# baseboardV0_1Part2.net
KiCad netlist of a schematic drawn in Altium Designer
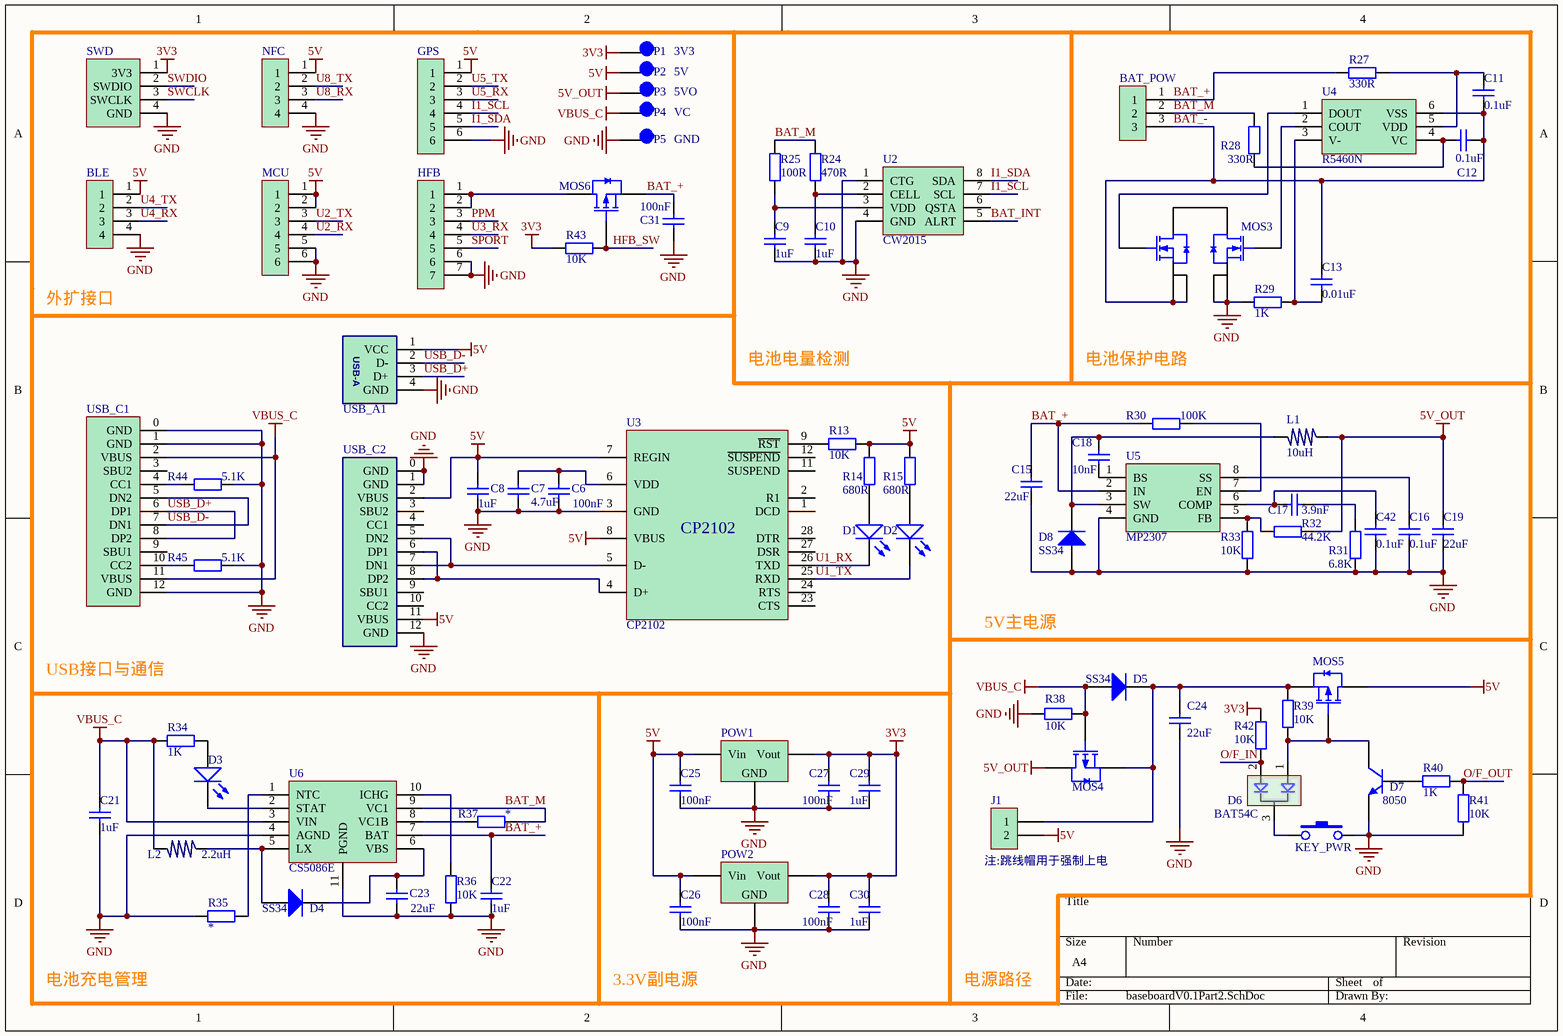
[diagram p0: baseboardV0.1Part2.SchDoc]

(export (version "E")
  (design (tool "Eeschema 10.0.6"))
  (components
    (comp (ref "BAT_POW")
      (value "XH2.54_3P_SMT_T")
      (footprint "XH2.54_3P_SMT_L")
      (libsource (lib "MT_Connector") (part "XH2.54_3P_SMT_T"))
    )
    (comp (ref "BLE")
      (value "SH1.25mm_4P")
      (footprint "SH1.25MM_4P")
      (libsource (lib "MT_Connector") (part "SH1.25mm_4P"))
    )
    (comp (ref "C6") (value "100nF") (footprint "0603_C") (libsource (lib "MT_Device") (part "0603_CAP")))
    (comp (ref "C7") (value "4.7uF") (footprint "0805_C") (libsource (lib "MT_Device") (part "0805_CAP")))
    (comp (ref "C8") (value "1uF") (footprint "0603_C") (libsource (lib "MT_Device") (part "0603_CAP")))
    (comp (ref "C9") (value "1uF") (footprint "0603_C") (libsource (lib "MT_Device") (part "0603_CAP")))
    (comp (ref "C10") (value "1uF") (footprint "0603_C") (libsource (lib "MT_Device") (part "0603_CAP")))
    (comp (ref "C11") (value "0.1uF") (footprint "0603_C") (libsource (lib "MT_Device") (part "0603_CAP")))
    (comp (ref "C12") (value "0.1uF") (footprint "0603_C") (libsource (lib "MT_Device") (part "0603_CAP")))
    (comp (ref "C13") (value "0.01uF") (footprint "0603_C") (libsource (lib "MT_Device") (part "0603_CAP")))
    (comp (ref "C15") (value "22uF") (footprint "0805_C") (libsource (lib "MT_Device") (part "0805_CAP")))
    (comp (ref "C16") (value "0.1uF") (footprint "0603_C") (libsource (lib "MT_Device") (part "0603_CAP")))
    (comp (ref "C17") (value "3.9nF") (footprint "0603_C") (libsource (lib "MT_Device") (part "0603_CAP")))
    (comp (ref "C18") (value "10nF") (footprint "0603_C") (libsource (lib "MT_Device") (part "0603_CAP")))
    (comp (ref "C19") (value "22uF") (footprint "0805_C") (libsource (lib "MT_Device") (part "0805_CAP")))
    (comp (ref "C21") (value "1uF") (footprint "0603_C") (libsource (lib "MT_Device") (part "0603_CAP")))
    (comp (ref "C22") (value "1uF") (footprint "0603_C") (libsource (lib "MT_Device") (part "0603_CAP")))
    (comp (ref "C23") (value "22uF") (footprint "0805_C") (libsource (lib "MT_Device") (part "0805_CAP")))
    (comp (ref "C24") (value "22uF") (footprint "0805_C") (libsource (lib "MT_Device") (part "0805_CAP")))
    (comp (ref "C25") (value "100nF") (footprint "0603_C") (libsource (lib "MT_Device") (part "0603_CAP")))
    (comp (ref "C26") (value "100nF") (footprint "0603_C") (libsource (lib "MT_Device") (part "0603_CAP")))
    (comp (ref "C27") (value "100nF") (footprint "0603_C") (libsource (lib "MT_Device") (part "0603_CAP")))
    (comp (ref "C28") (value "100nF") (footprint "0603_C") (libsource (lib "MT_Device") (part "0603_CAP")))
    (comp (ref "C29") (value "1uF") (footprint "0603_C") (libsource (lib "MT_Device") (part "0603_CAP")))
    (comp (ref "C30") (value "1uF") (footprint "0603_C") (libsource (lib "MT_Device") (part "0603_CAP")))
    (comp (ref "C31") (value "100nF") (footprint "0603_C") (libsource (lib "MT_Device") (part "0603_CAP")))
    (comp (ref "C42") (value "0.1uF") (footprint "0603_C") (libsource (lib "MT_Device") (part "0603_CAP")))
    (comp (ref "D1")
      (value "0805_LED")
      (footprint "0805_LED")
      (libsource (lib "MT_Device") (part "0805_LED"))
    )
    (comp (ref "D2")
      (value "0805_LED")
      (footprint "0805_LED")
      (libsource (lib "MT_Device") (part "0805_LED"))
    )
    (comp (ref "D3")
      (value "0805_LED")
      (footprint "0805_LED")
      (libsource (lib "MT_Device") (part "0805_LED"))
    )
    (comp (ref "D4") (value "SS34") (footprint "DO214_SMC") (libsource (lib "MT_Device") (part "SS34_DO214")))
    (comp (ref "D5") (value "SS34") (footprint "DO214_SMC") (libsource (lib "MT_Device") (part "SS34_DO214")))
    (comp (ref "D6") (value "BAT54C") (footprint "BAT54C") (libsource (lib "MT_Device") (part "BAT54C")))
    (comp (ref "D7")
      (value "8050")
      (footprint "SOT23")
      (libsource (lib "MT_Device") (part "NPN_SS8050_SOT23"))
    )
    (comp (ref "D8") (value "SS34") (footprint "DO214_SMC") (libsource (lib "MT_Device") (part "SS34_DO214")))
    (comp (ref "GPS")
      (value "SH1.25mm_6P")
      (footprint "SH1.25MM_6P")
      (libsource (lib "MT_Connector") (part "SH1.25mm_6P"))
    )
    (comp (ref "HFB")
      (value "SH1.25mm_7P")
      (footprint "SH1.25MM_7P")
      (libsource (lib "MT_Connector") (part "SH1.25mm_7P"))
    )
    (comp (ref "J1")
      (value "Header_2.54_2P")
      (footprint "HDR1_2P")
      (libsource (lib "MT_Connector") (part "Header_2.54_2P"))
    )
    (comp (ref "KEY_PWR")
      (value "KEY_S_6*6")
      (footprint "KEY_S_6*6")
      (libsource (lib "MT_Device") (part "KEY_S_6*6"))
    )
    (comp (ref "L1") (value "10uH") (footprint "0630_L") (libsource (lib "MT_Device") (part "0630_L")))
    (comp (ref "L2") (value "2.2uH") (footprint "0630_L") (libsource (lib "MT_Device") (part "0630_L")))
    (comp (ref "MCU")
      (value "SH1.25mm_6P")
      (footprint "SH1.25MM_6P")
      (libsource (lib "MT_Connector") (part "SH1.25mm_6P"))
    )
    (comp (ref "MOS3")
      (value "MOSN_8205A_TSSOP8")
      (footprint "TSSOP-8")
      (libsource (lib "MT_Device") (part "MOSN_8205A_TSSOP8"))
    )
    (comp (ref "MOS4")
      (value "MOSP_AO4419_SOIC8")
      (footprint "SOIC8_MOS")
      (libsource (lib "MT_Device") (part "MOSP_AO4419_SOIC8"))
    )
    (comp (ref "MOS5")
      (value "MOSP_AO4419_SOIC8")
      (footprint "SOIC8_MOS")
      (libsource (lib "MT_Device") (part "MOSP_AO4419_SOIC8"))
    )
    (comp (ref "MOS6")
      (value "MOSP_AO4419_SOIC8")
      (footprint "SOIC8_MOS")
      (libsource (lib "MT_Device") (part "MOSP_AO4419_SOIC8"))
    )
    (comp (ref "MTSWD") (value "SWD") (footprint "MT_SWD_1") (libsource (lib "MT_Module") (part "MT_SWD_1")))
    (comp (ref "NFC")
      (value "SH1.25mm_4P")
      (footprint "SH1.25MM_4P")
      (libsource (lib "MT_Connector") (part "SH1.25mm_4P"))
    )
    (comp (ref "P1")
      (value "3V3")
      (footprint "TEST_POINT_2mm")
      (libsource (lib "MT_Connector") (part "TEST_POINT_2mm"))
    )
    (comp (ref "P2")
      (value "5V")
      (footprint "TEST_POINT_2mm")
      (libsource (lib "MT_Connector") (part "TEST_POINT_2mm"))
    )
    (comp (ref "P3")
      (value "5VO")
      (footprint "TEST_POINT_2mm")
      (libsource (lib "MT_Connector") (part "TEST_POINT_2mm"))
    )
    (comp (ref "P4")
      (value "VC")
      (footprint "TEST_POINT_2mm")
      (libsource (lib "MT_Connector") (part "TEST_POINT_2mm"))
    )
    (comp (ref "P5")
      (value "GND")
      (footprint "TEST_POINT_2mm")
      (libsource (lib "MT_Connector") (part "TEST_POINT_2mm"))
    )
    (comp (ref "POW1")
      (value "AMS1117_3.3")
      (footprint "SOT223")
      (libsource (lib "MT_Device") (part "AMS1117_3.3"))
    )
    (comp (ref "POW2")
      (value "AMS1117_3.3")
      (footprint "SOT223")
      (libsource (lib "MT_Device") (part "AMS1117_3.3"))
    )
    (comp (ref "R13") (value "10K") (footprint "0603_R") (libsource (lib "") (part "0603_RES_3")))
    (comp (ref "R14") (value "680R") (footprint "0603_R") (libsource (lib "") (part "0603_RES_1")))
    (comp (ref "R15") (value "680R") (footprint "0603_R") (libsource (lib "") (part "0603_RES_1")))
    (comp (ref "R24") (value "470R") (footprint "0603_R") (libsource (lib "MT_Device") (part "0603_RES")))
    (comp (ref "R25") (value "100R") (footprint "0603_R") (libsource (lib "MT_Device") (part "0603_RES")))
    (comp (ref "R27") (value "330R") (footprint "0603_R") (libsource (lib "") (part "0603_RES_2")))
    (comp (ref "R28") (value "330R") (footprint "0603_R") (libsource (lib "") (part "0603_RES_1")))
    (comp (ref "R29") (value "1K") (footprint "0603_R") (libsource (lib "") (part "0603_RES_2")))
    (comp (ref "R30") (value "100K") (footprint "0603_R") (libsource (lib "") (part "0603_RES_2")))
    (comp (ref "R31") (value "6.8K") (footprint "0603_R") (libsource (lib "") (part "0603_RES_1")))
    (comp (ref "R32") (value "44.2K") (footprint "0603_R") (libsource (lib "") (part "0603_RES_3")))
    (comp (ref "R33") (value "10K") (footprint "0603_R") (libsource (lib "") (part "0603_RES_1")))
    (comp (ref "R34") (value "1K") (footprint "0603_R") (libsource (lib "") (part "0603_RES_3")))
    (comp (ref "R35") (value "*") (footprint "0603_R") (libsource (lib "") (part "0603_RES_3")))
    (comp (ref "R36") (value "10K") (footprint "0603_R") (libsource (lib "MT_Device") (part "0603_RES")))
    (comp (ref "R37") (value "*") (footprint "0603_R") (libsource (lib "") (part "0603_RES_3")))
    (comp (ref "R38") (value "10K") (footprint "0603_R") (libsource (lib "") (part "0603_RES_3")))
    (comp (ref "R39") (value "10K") (footprint "0603_R") (libsource (lib "") (part "0603_RES_1")))
    (comp (ref "R40") (value "1K") (footprint "0603_R") (libsource (lib "") (part "0603_RES_2")))
    (comp (ref "R41") (value "10K") (footprint "0603_R") (libsource (lib "") (part "0603_RES_1")))
    (comp (ref "R42") (value "10K") (footprint "0603_R") (libsource (lib "") (part "0603_RES_1")))
    (comp (ref "R43") (value "10K") (footprint "0603_R") (libsource (lib "") (part "0603_RES_2")))
    (comp (ref "R44") (value "5.1K") (footprint "0603_R") (libsource (lib "") (part "0603_RES_2")))
    (comp (ref "R45") (value "5.1K") (footprint "0603_R") (libsource (lib "") (part "0603_RES_2")))
    (comp (ref "U2")
      (value "CW2015")
      (footprint "CW2015_TDFN")
      (libsource (lib "MT_Chip") (part "CW2015_TDFN"))
    )
    (comp (ref "U3") (value "CP2102") (footprint "QFN28") (libsource (lib "MT_Chip") (part "CP2102_QFN28")))
    (comp (ref "U4")
      (value "R5460N")
      (footprint "SOT_23_6")
      (description "2-CELL PROTECTOR")
      (libsource (lib "MT_Chip") (part "R5460N"))
    )
    (comp (ref "U5") (value "MP2307") (footprint "SOIC8N") (libsource (lib "MT_Chip") (part "MP2307")))
    (comp (ref "U6") (value "CS5086E") (footprint "ESOP10L") (libsource (lib "MT_Chip") (part "CS5086E")))
    (comp (ref "USB_A1")
      (value "USB_A_SMT")
      (footprint "USB_A_SMT")
      (libsource (lib "MT_Device") (part "USB_A_SMT"))
    )
    (comp (ref "USB_C1")
      (value "USB_C_16P_SMT")
      (footprint "USB_C_16PIN_SMT")
      (libsource (lib "MT_Device") (part "USB_C_16P_SMT"))
    )
    (comp (ref "USB_C2")
      (value "USB_C_16P_SMT")
      (footprint "USB_C_16PIN_SMT")
      (libsource (lib "") (part "USB_C_16P_SMT_1"))
    )
  )
  (nets
    (net (code "1") (name "/BAT_+") (class "Default")
      (node (ref "BAT_POW") (pin "1") (pinfunction "1_1") (pintype "passive"))
      (node (ref "C15") (pin "2") (pinfunction "2_2") (pintype "passive"))
      (node (ref "C22") (pin "2") (pinfunction "2_2") (pintype "passive"))
      (node (ref "C31") (pin "2") (pinfunction "2_2") (pintype "passive"))
      (node (ref "MOS6") (pin "3") (pinfunction "S_3") (pintype "passive"))
      (node (ref "R27") (pin "2") (pinfunction "2_2") (pintype "passive"))
      (node (ref "R30") (pin "2") (pinfunction "2_2") (pintype "passive"))
      (node (ref "U5") (pin "2") (pinfunction "IN_2") (pintype "passive"))
      (node (ref "U6") (pin "7") (pinfunction "BAT_7") (pintype "passive"))
    )
    (net (code "2") (name "/BAT_-") (class "Default")
      (node (ref "BAT_POW") (pin "3") (pinfunction "3_3") (pintype "passive"))
      (node (ref "C11") (pin "1") (pinfunction "1_1") (pintype "passive"))
      (node (ref "C12") (pin "1") (pinfunction "1_1") (pintype "passive"))
      (node (ref "C13") (pin "2") (pinfunction "2_2") (pintype "passive"))
      (node (ref "MOS3") (pin "2") (pinfunction "S1_2") (pintype "passive"))
      (node (ref "MOS3") (pin "3") (pinfunction "S1_3") (pintype "passive"))
      (node (ref "U4") (pin "6") (pinfunction "VSS_6") (pintype "passive"))
    )
    (net (code "3") (name "/BAT_INT") (class "Default")
      (node (ref "U2") (pin "5") (pinfunction "ALRT_5") (pintype "passive"))
    )
    (net (code "4") (name "/BAT_M") (class "Default")
      (node (ref "BAT_POW") (pin "2") (pinfunction "2_2") (pintype "passive"))
      (node (ref "R24") (pin "1") (pinfunction "1_1") (pintype "passive"))
      (node (ref "R25") (pin "1") (pinfunction "1_1") (pintype "passive"))
      (node (ref "R28") (pin "2") (pinfunction "2_2") (pintype "passive"))
      (node (ref "R37") (pin "2") (pinfunction "2_2") (pintype "passive"))
      (node (ref "U6") (pin "9") (pinfunction "VC1_9") (pintype "passive"))
    )
    (net (code "5") (name "/HFB_SW") (class "Default")
      (node (ref "MOS6") (pin "1") (pinfunction "G_1") (pintype "passive"))
      (node (ref "R43") (pin "1") (pinfunction "1_1") (pintype "passive"))
    )
    (net (code "6") (name "/I1_SCL") (class "Default")
      (node (ref "GPS") (pin "4") (pinfunction "4_4") (pintype "passive"))
      (node (ref "U2") (pin "7") (pinfunction "SCL_7") (pintype "passive"))
    )
    (net (code "7") (name "/I1_SDA") (class "Default")
      (node (ref "GPS") (pin "5") (pinfunction "5_5") (pintype "passive"))
      (node (ref "U2") (pin "8") (pinfunction "SDA_8") (pintype "passive"))
    )
    (net (code "8") (name "/O{slash}F_IN") (class "Default")
      (node (ref "D6") (pin "2") (pinfunction "2_2") (pintype "passive"))
      (node (ref "R42") (pin "1") (pinfunction "1_1") (pintype "passive"))
    )
    (net (code "9") (name "/O{slash}F_OUT") (class "Default")
      (node (ref "R40") (pin "1") (pinfunction "1_1") (pintype "passive"))
      (node (ref "R41") (pin "2") (pinfunction "2_2") (pintype "passive"))
    )
    (net (code "10") (name "/PPM") (class "Default")
      (node (ref "HFB") (pin "3") (pinfunction "3_3") (pintype "passive"))
    )
    (net (code "11") (name "/SPORT") (class "Default")
      (node (ref "HFB") (pin "5") (pinfunction "5_5") (pintype "passive"))
    )
    (net (code "12") (name "/SWCLK") (class "Default")
      (node (ref "MTSWD") (pin "3") (pinfunction "SWCLK_3") (pintype "passive"))
    )
    (net (code "13") (name "/SWDIO") (class "Default")
      (node (ref "MTSWD") (pin "2") (pinfunction "SWDIO_2") (pintype "passive"))
    )
    (net (code "14") (name "/U1_RX") (class "Default")
      (node (ref "D1") (pin "K") (pinfunction "K_K") (pintype "passive"))
      (node (ref "U3") (pin "26") (pinfunction "TXD_26") (pintype "passive"))
    )
    (net (code "15") (name "/U1_TX") (class "Default")
      (node (ref "D2") (pin "K") (pinfunction "K_K") (pintype "passive"))
      (node (ref "U3") (pin "25") (pinfunction "RXD_25") (pintype "passive"))
    )
    (net (code "16") (name "/U2_RX") (class "Default")
      (node (ref "MCU") (pin "4") (pinfunction "4_4") (pintype "passive"))
    )
    (net (code "17") (name "/U2_TX") (class "Default")
      (node (ref "MCU") (pin "3") (pinfunction "3_3") (pintype "passive"))
    )
    (net (code "18") (name "/U3_RX") (class "Default")
      (node (ref "HFB") (pin "4") (pinfunction "4_4") (pintype "passive"))
    )
    (net (code "19") (name "/U4_RX") (class "Default")
      (node (ref "BLE") (pin "3") (pinfunction "3_3") (pintype "passive"))
    )
    (net (code "20") (name "/U4_TX") (class "Default")
      (node (ref "BLE") (pin "2") (pinfunction "2_2") (pintype "passive"))
    )
    (net (code "21") (name "/U5_RX") (class "Default")
      (node (ref "GPS") (pin "3") (pinfunction "3_3") (pintype "passive"))
    )
    (net (code "22") (name "/U5_TX") (class "Default")
      (node (ref "GPS") (pin "2") (pinfunction "2_2") (pintype "passive"))
    )
    (net (code "23") (name "/U8_RX") (class "Default")
      (node (ref "NFC") (pin "3") (pinfunction "3_3") (pintype "passive"))
    )
    (net (code "24") (name "/U8_TX") (class "Default")
      (node (ref "NFC") (pin "2") (pinfunction "2_2") (pintype "passive"))
    )
    (net (code "25") (name "/USB_D+") (class "Default")
      (node (ref "USB_A1") (pin "3") (pinfunction "D+_3") (pintype "passive"))
      (node (ref "USB_C1") (pin "6") (pinfunction "DP1_6") (pintype "passive"))
      (node (ref "USB_C1") (pin "8") (pinfunction "DP2_8") (pintype "passive"))
    )
    (net (code "26") (name "/USB_D-") (class "Default")
      (node (ref "USB_A1") (pin "2") (pinfunction "D-_2") (pintype "passive"))
      (node (ref "USB_C1") (pin "5") (pinfunction "DN2_5") (pintype "passive"))
      (node (ref "USB_C1") (pin "7") (pinfunction "DN1_7") (pintype "passive"))
    )
    (net (code "27") (name "3V3") (class "Default")
      (node (ref "C27") (pin "2") (pinfunction "2_2") (pintype "passive"))
      (node (ref "C28") (pin "2") (pinfunction "2_2") (pintype "passive"))
      (node (ref "C29") (pin "2") (pinfunction "2_2") (pintype "passive"))
      (node (ref "C30") (pin "2") (pinfunction "2_2") (pintype "passive"))
      (node (ref "MTSWD") (pin "1") (pinfunction "3V3_1") (pintype "passive"))
      (node (ref "P1") (pin "1") (pinfunction "1_1") (pintype "passive"))
      (node (ref "POW1") (pin "2") (pinfunction "Vout_2") (pintype "passive"))
      (node (ref "POW2") (pin "2") (pinfunction "Vout_2") (pintype "passive"))
      (node (ref "R42") (pin "2") (pinfunction "2_2") (pintype "passive"))
      (node (ref "R43") (pin "2") (pinfunction "2_2") (pintype "passive"))
    )
    (net (code "28") (name "5V") (class "Default")
      (node (ref "BLE") (pin "1") (pinfunction "1_1") (pintype "passive"))
      (node (ref "C25") (pin "2") (pinfunction "2_2") (pintype "passive"))
      (node (ref "C26") (pin "2") (pinfunction "2_2") (pintype "passive"))
      (node (ref "C8") (pin "2") (pinfunction "2_2") (pintype "passive"))
      (node (ref "GPS") (pin "1") (pinfunction "1_1") (pintype "passive"))
      (node (ref "J1") (pin "2") (pinfunction "2_2") (pintype "passive"))
      (node (ref "MCU") (pin "1") (pinfunction "1_1") (pintype "passive"))
      (node (ref "MCU") (pin "2") (pinfunction "2_2") (pintype "passive"))
      (node (ref "MOS5") (pin "2") (pinfunction "D_2") (pintype "passive"))
      (node (ref "NFC") (pin "1") (pinfunction "1_1") (pintype "passive"))
      (node (ref "P2") (pin "1") (pinfunction "1_1") (pintype "passive"))
      (node (ref "POW1") (pin "3") (pinfunction "Vin_3") (pintype "passive"))
      (node (ref "POW2") (pin "3") (pinfunction "Vin_3") (pintype "passive"))
      (node (ref "R13") (pin "2") (pinfunction "2_2") (pintype "passive"))
      (node (ref "R14") (pin "2") (pinfunction "2_2") (pintype "passive"))
      (node (ref "R15") (pin "2") (pinfunction "2_2") (pintype "passive"))
      (node (ref "U3") (pin "7") (pinfunction "REGIN_7") (pintype "passive"))
      (node (ref "U3") (pin "8") (pinfunction "VBUS_8") (pintype "passive"))
      (node (ref "USB_A1") (pin "1") (pinfunction "VCC_1") (pintype "passive"))
      (node (ref "USB_C2") (pin "11") (pinfunction "VBUS_11") (pintype "passive"))
      (node (ref "USB_C2") (pin "2") (pinfunction "VBUS_2") (pintype "passive"))
    )
    (net (code "29") (name "5V_OUT") (class "Default")
      (node (ref "C19") (pin "2") (pinfunction "2_2") (pintype "passive"))
      (node (ref "L1") (pin "1") (pintype "passive"))
      (node (ref "MOS4") (pin "2") (pinfunction "D_2") (pintype "passive"))
      (node (ref "P3") (pin "1") (pinfunction "1_1") (pintype "passive"))
      (node (ref "R32") (pin "2") (pinfunction "2_2") (pintype "passive"))
    )
    (net (code "30") (name "GND") (class "Default")
      (node (ref "BLE") (pin "4") (pinfunction "4_4") (pintype "passive"))
      (node (ref "C10") (pin "1") (pinfunction "1_1") (pintype "passive"))
      (node (ref "C15") (pin "1") (pinfunction "1_1") (pintype "passive"))
      (node (ref "C16") (pin "2") (pinfunction "2_2") (pintype "passive"))
      (node (ref "C19") (pin "1") (pinfunction "1_1") (pintype "passive"))
      (node (ref "C21") (pin "1") (pinfunction "1_1") (pintype "passive"))
      (node (ref "C22") (pin "1") (pinfunction "1_1") (pintype "passive"))
      (node (ref "C23") (pin "1") (pinfunction "1_1") (pintype "passive"))
      (node (ref "C24") (pin "1") (pinfunction "1_1") (pintype "passive"))
      (node (ref "C25") (pin "1") (pinfunction "1_1") (pintype "passive"))
      (node (ref "C26") (pin "1") (pinfunction "1_1") (pintype "passive"))
      (node (ref "C27") (pin "1") (pinfunction "1_1") (pintype "passive"))
      (node (ref "C28") (pin "1") (pinfunction "1_1") (pintype "passive"))
      (node (ref "C29") (pin "1") (pinfunction "1_1") (pintype "passive"))
      (node (ref "C30") (pin "1") (pinfunction "1_1") (pintype "passive"))
      (node (ref "C31") (pin "1") (pinfunction "1_1") (pintype "passive"))
      (node (ref "C42") (pin "2") (pinfunction "2_2") (pintype "passive"))
      (node (ref "C6") (pin "1") (pinfunction "1_1") (pintype "passive"))
      (node (ref "C7") (pin "2") (pinfunction "2_2") (pintype "passive"))
      (node (ref "C8") (pin "1") (pinfunction "1_1") (pintype "passive"))
      (node (ref "C9") (pin "1") (pinfunction "1_1") (pintype "passive"))
      (node (ref "D7") (pin "2") (pinfunction "E_2") (pintype "passive"))
      (node (ref "D8") (pin "1") (pinfunction "A_1") (pintype "passive"))
      (node (ref "GPS") (pin "6") (pinfunction "6_6") (pintype "passive"))
      (node (ref "HFB") (pin "6") (pinfunction "6_6") (pintype "passive"))
      (node (ref "HFB") (pin "7") (pinfunction "7_7") (pintype "passive"))
      (node (ref "KEY_PWR") (pin "2") (pinfunction "2_2") (pintype "passive"))
      (node (ref "MCU") (pin "5") (pinfunction "5_5") (pintype "passive"))
      (node (ref "MCU") (pin "6") (pinfunction "6_6") (pintype "passive"))
      (node (ref "MOS3") (pin "6") (pinfunction "S2_6") (pintype "passive"))
      (node (ref "MOS3") (pin "7") (pinfunction "S2_7") (pintype "passive"))
      (node (ref "MTSWD") (pin "4") (pinfunction "GND_4") (pintype "passive"))
      (node (ref "NFC") (pin "4") (pinfunction "4_4") (pintype "passive"))
      (node (ref "P5") (pin "1") (pinfunction "1_1") (pintype "passive"))
      (node (ref "POW1") (pin "1") (pinfunction "GND_1") (pintype "passive"))
      (node (ref "POW2") (pin "1") (pinfunction "GND_1") (pintype "passive"))
      (node (ref "R29") (pin "2") (pinfunction "2_2") (pintype "passive"))
      (node (ref "R31") (pin "1") (pinfunction "1_1") (pintype "passive"))
      (node (ref "R33") (pin "1") (pinfunction "1_1") (pintype "passive"))
      (node (ref "R35") (pin "1") (pinfunction "1_1") (pintype "passive"))
      (node (ref "R36") (pin "2") (pinfunction "2_2") (pintype "passive"))
      (node (ref "R38") (pin "1") (pinfunction "1_1") (pintype "passive"))
      (node (ref "R41") (pin "1") (pinfunction "1_1") (pintype "passive"))
      (node (ref "R44") (pin "1") (pinfunction "1_1") (pintype "passive"))
      (node (ref "R45") (pin "1") (pinfunction "1_1") (pintype "passive"))
      (node (ref "U2") (pin "1") (pinfunction "CTG_1") (pintype "passive"))
      (node (ref "U2") (pin "4") (pinfunction "GND_4") (pintype "passive"))
      (node (ref "U3") (pin "3") (pinfunction "GND_3") (pintype "passive"))
      (node (ref "U5") (pin "4") (pinfunction "GND_4") (pintype "passive"))
      (node (ref "U6") (pin "11") (pinfunction "PGND_11") (pintype "passive"))
      (node (ref "U6") (pin "4") (pinfunction "AGND_4") (pintype "passive"))
      (node (ref "USB_A1") (pin "4") (pinfunction "GND_4") (pintype "passive"))
      (node (ref "USB_C1") (pin "0") (pinfunction "GND_0") (pintype "passive"))
      (node (ref "USB_C1") (pin "1") (pinfunction "GND_1") (pintype "passive"))
      (node (ref "USB_C1") (pin "12") (pinfunction "GND_12") (pintype "passive"))
      (node (ref "USB_C2") (pin "0") (pinfunction "GND_0") (pintype "passive"))
      (node (ref "USB_C2") (pin "1") (pinfunction "GND_1") (pintype "passive"))
      (node (ref "USB_C2") (pin "12") (pinfunction "GND_12") (pintype "passive"))
    )
    (net (code "31") (name "Net-(C17-Pad2)") (class "Default")
      (node (ref "C17") (pin "2") (pinfunction "2_2") (pintype "passive"))
      (node (ref "R31") (pin "2") (pinfunction "2_2") (pintype "passive"))
    )
    (net (code "32") (name "Net-(D1-PadA)") (class "Default")
      (node (ref "D1") (pin "A") (pinfunction "A_A") (pintype "passive"))
      (node (ref "R14") (pin "1") (pinfunction "1_1") (pintype "passive"))
    )
    (net (code "33") (name "Net-(D2-PadA)") (class "Default")
      (node (ref "D2") (pin "A") (pinfunction "A_A") (pintype "passive"))
      (node (ref "R15") (pin "1") (pinfunction "1_1") (pintype "passive"))
    )
    (net (code "34") (name "Net-(D3-PadA)") (class "Default")
      (node (ref "D3") (pin "A") (pinfunction "A_A") (pintype "passive"))
      (node (ref "R34") (pin "2") (pinfunction "2_2") (pintype "passive"))
    )
    (net (code "35") (name "Net-(D4-A)") (class "Default")
      (node (ref "D4") (pin "1") (pinfunction "A_1") (pintype "passive"))
      (node (ref "L2") (pin "1") (pintype "passive"))
      (node (ref "U6") (pin "5") (pinfunction "LX_5") (pintype "passive"))
    )
    (net (code "36") (name "Net-(D4-K)") (class "Default")
      (node (ref "C23") (pin "2") (pinfunction "2_2") (pintype "passive"))
      (node (ref "D4") (pin "2") (pinfunction "K_2") (pintype "passive"))
      (node (ref "U6") (pin "6") (pinfunction "VBS_6") (pintype "passive"))
    )
    (net (code "37") (name "Net-(D5-K)") (class "Default")
      (node (ref "C24") (pin "2") (pinfunction "2_2") (pintype "passive"))
      (node (ref "D5") (pin "2") (pinfunction "K_2") (pintype "passive"))
      (node (ref "J1") (pin "1") (pinfunction "1_1") (pintype "passive"))
      (node (ref "MOS4") (pin "3") (pinfunction "S_3") (pintype "passive"))
      (node (ref "MOS5") (pin "3") (pinfunction "S_3") (pintype "passive"))
      (node (ref "R39") (pin "2") (pinfunction "2_2") (pintype "passive"))
    )
    (net (code "38") (name "Net-(D6-Pad3)") (class "Default")
      (node (ref "D6") (pin "3") (pinfunction "3_3") (pintype "passive"))
      (node (ref "KEY_PWR") (pin "1") (pinfunction "1_1") (pintype "passive"))
    )
    (net (code "39") (name "Net-(D7-B)") (class "Default")
      (node (ref "D7") (pin "1") (pinfunction "B_1") (pintype "passive"))
      (node (ref "R40") (pin "2") (pinfunction "2_2") (pintype "passive"))
    )
    (net (code "40") (name "Net-(D7-C)") (class "Default")
      (node (ref "D6") (pin "1") (pinfunction "1_1") (pintype "passive"))
      (node (ref "D7") (pin "3") (pinfunction "C_3") (pintype "passive"))
      (node (ref "MOS5") (pin "1") (pinfunction "G_1") (pintype "passive"))
      (node (ref "R39") (pin "1") (pinfunction "1_1") (pintype "passive"))
    )
    (net (code "41") (name "Net-(D8-K)") (class "Default")
      (node (ref "C18") (pin "1") (pinfunction "1_1") (pintype "passive"))
      (node (ref "D8") (pin "2") (pinfunction "K_2") (pintype "passive"))
      (node (ref "L1") (pin "2") (pintype "passive"))
      (node (ref "U5") (pin "3") (pinfunction "SW_3") (pintype "passive"))
    )
    (net (code "42") (name "Net-(MOS3-G1)") (class "Default")
      (node (ref "MOS3") (pin "4") (pinfunction "G1_4") (pintype "passive"))
      (node (ref "U4") (pin "1") (pinfunction "DOUT_1") (pintype "passive"))
    )
    (net (code "43") (name "Net-(MOS3-G2)") (class "Default")
      (node (ref "MOS3") (pin "5") (pinfunction "G2_5") (pintype "passive"))
      (node (ref "U4") (pin "2") (pinfunction "COUT_2") (pintype "passive"))
    )
    (net (code "44") (name "Net-(MOS6-D)") (class "Default")
      (node (ref "HFB") (pin "1") (pinfunction "1_1") (pintype "passive"))
      (node (ref "HFB") (pin "2") (pinfunction "2_2") (pintype "passive"))
      (node (ref "MOS6") (pin "2") (pinfunction "D_2") (pintype "passive"))
    )
    (net (code "45") (name "Net-(U2-CELL)") (class "Default")
      (node (ref "C10") (pin "2") (pinfunction "2_2") (pintype "passive"))
      (node (ref "R24") (pin "2") (pinfunction "2_2") (pintype "passive"))
      (node (ref "U2") (pin "2") (pinfunction "CELL_2") (pintype "passive"))
    )
    (net (code "46") (name "Net-(U2-VDD)") (class "Default")
      (node (ref "C9") (pin "2") (pinfunction "2_2") (pintype "passive"))
      (node (ref "R25") (pin "2") (pinfunction "2_2") (pintype "passive"))
      (node (ref "U2") (pin "3") (pinfunction "VDD_3") (pintype "passive"))
    )
    (net (code "47") (name "Net-(U3-D+)") (class "Default")
      (node (ref "U3") (pin "4") (pinfunction "D+_4") (pintype "passive"))
      (node (ref "USB_C2") (pin "6") (pinfunction "DP1_6") (pintype "passive"))
      (node (ref "USB_C2") (pin "8") (pinfunction "DP2_8") (pintype "passive"))
    )
    (net (code "48") (name "Net-(U3-D-)") (class "Default")
      (node (ref "U3") (pin "5") (pinfunction "D-_5") (pintype "passive"))
      (node (ref "USB_C2") (pin "5") (pinfunction "DN2_5") (pintype "passive"))
      (node (ref "USB_C2") (pin "7") (pinfunction "DN1_7") (pintype "passive"))
    )
    (net (code "49") (name "Net-(U3-VDD)") (class "Default")
      (node (ref "C6") (pin "2") (pinfunction "2_2") (pintype "passive"))
      (node (ref "C7") (pin "1") (pinfunction "1_1") (pintype "passive"))
      (node (ref "U3") (pin "6") (pinfunction "VDD_6") (pintype "passive"))
    )
    (net (code "50") (name "Net-(U3-~{RST})") (class "Default")
      (node (ref "R13") (pin "1") (pinfunction "1_1") (pintype "passive"))
      (node (ref "U3") (pin "9") (pinfunction "~{RST}_9") (pintype "passive"))
    )
    (net (code "51") (name "Net-(U4-V-)") (class "Default")
      (node (ref "C13") (pin "1") (pinfunction "1_1") (pintype "passive"))
      (node (ref "R29") (pin "1") (pinfunction "1_1") (pintype "passive"))
      (node (ref "U4") (pin "3") (pinfunction "V-_3") (pintype "passive"))
    )
    (net (code "52") (name "Net-(U4-VC)") (class "Default")
      (node (ref "C12") (pin "2") (pinfunction "2_2") (pintype "passive"))
      (node (ref "R28") (pin "1") (pinfunction "1_1") (pintype "passive"))
      (node (ref "U4") (pin "4") (pinfunction "VC_4") (pintype "passive"))
    )
    (net (code "53") (name "Net-(U4-VDD)") (class "Default")
      (node (ref "C11") (pin "2") (pinfunction "2_2") (pintype "passive"))
      (node (ref "R27") (pin "1") (pinfunction "1_1") (pintype "passive"))
      (node (ref "U4") (pin "5") (pinfunction "VDD_5") (pintype "passive"))
    )
    (net (code "54") (name "Net-(U5-BS)") (class "Default")
      (node (ref "C18") (pin "2") (pinfunction "2_2") (pintype "passive"))
      (node (ref "U5") (pin "1") (pinfunction "BS_1") (pintype "passive"))
    )
    (net (code "55") (name "Net-(U5-COMP)") (class "Default")
      (node (ref "C17") (pin "1") (pinfunction "1_1") (pintype "passive"))
      (node (ref "C42") (pin "1") (pinfunction "1_1") (pintype "passive"))
      (node (ref "U5") (pin "6") (pinfunction "COMP_6") (pintype "passive"))
    )
    (net (code "56") (name "Net-(U5-EN)") (class "Default")
      (node (ref "R30") (pin "1") (pinfunction "1_1") (pintype "passive"))
      (node (ref "U5") (pin "7") (pinfunction "EN_7") (pintype "passive"))
    )
    (net (code "57") (name "Net-(U5-FB)") (class "Default")
      (node (ref "R32") (pin "1") (pinfunction "1_1") (pintype "passive"))
      (node (ref "R33") (pin "2") (pinfunction "2_2") (pintype "passive"))
      (node (ref "U5") (pin "5") (pinfunction "FB_5") (pintype "passive"))
    )
    (net (code "58") (name "Net-(U5-SS)") (class "Default")
      (node (ref "C16") (pin "1") (pinfunction "1_1") (pintype "passive"))
      (node (ref "U5") (pin "8") (pinfunction "SS_8") (pintype "passive"))
    )
    (net (code "59") (name "Net-(U6-ICHG)") (class "Default")
      (node (ref "R36") (pin "1") (pinfunction "1_1") (pintype "passive"))
      (node (ref "U6") (pin "10") (pinfunction "ICHG_10") (pintype "passive"))
    )
    (net (code "60") (name "Net-(U6-NTC)") (class "Default")
      (node (ref "R35") (pin "2") (pinfunction "2_2") (pintype "passive"))
      (node (ref "U6") (pin "1") (pinfunction "NTC_1") (pintype "passive"))
    )
    (net (code "61") (name "Net-(U6-STAT)") (class "Default")
      (node (ref "D3") (pin "K") (pinfunction "K_K") (pintype "passive"))
      (node (ref "U6") (pin "2") (pinfunction "STAT_2") (pintype "passive"))
    )
    (net (code "62") (name "Net-(U6-VC1B)") (class "Default")
      (node (ref "R37") (pin "1") (pinfunction "1_1") (pintype "passive"))
      (node (ref "U6") (pin "8") (pinfunction "VC1B_8") (pintype "passive"))
    )
    (net (code "63") (name "Net-(USB_C1-CC1)") (class "Default")
      (node (ref "R44") (pin "2") (pinfunction "2_2") (pintype "passive"))
      (node (ref "USB_C1") (pin "4") (pinfunction "CC1_4") (pintype "passive"))
    )
    (net (code "64") (name "Net-(USB_C1-CC2)") (class "Default")
      (node (ref "R45") (pin "2") (pinfunction "2_2") (pintype "passive"))
      (node (ref "USB_C1") (pin "10") (pinfunction "CC2_10") (pintype "passive"))
    )
    (net (code "65") (name "VBUS_C") (class "Default")
      (node (ref "C21") (pin "2") (pinfunction "2_2") (pintype "passive"))
      (node (ref "D5") (pin "1") (pinfunction "A_1") (pintype "passive"))
      (node (ref "L2") (pin "2") (pintype "passive"))
      (node (ref "MOS4") (pin "1") (pinfunction "G_1") (pintype "passive"))
      (node (ref "P4") (pin "1") (pinfunction "1_1") (pintype "passive"))
      (node (ref "R34") (pin "1") (pinfunction "1_1") (pintype "passive"))
      (node (ref "R38") (pin "2") (pinfunction "2_2") (pintype "passive"))
      (node (ref "U6") (pin "3") (pinfunction "VIN_3") (pintype "passive"))
      (node (ref "USB_C1") (pin "11") (pinfunction "VBUS_11") (pintype "passive"))
      (node (ref "USB_C1") (pin "2") (pinfunction "VBUS_2") (pintype "passive"))
    )
    (net (code "66") (name "unconnected-(MOS3-D1-Pad1)") (class "Default")
      (node (ref "MOS3") (pin "1") (pinfunction "D1_1") (pintype "passive"))
    )
    (net (code "67") (name "unconnected-(MOS3-D2-Pad8)") (class "Default")
      (node (ref "MOS3") (pin "8") (pinfunction "D2_8") (pintype "passive"))
    )
    (net (code "68") (name "unconnected-(U2-QSTA-Pad6)") (class "Default")
      (node (ref "U2") (pin "6") (pinfunction "QSTA_6") (pintype "passive"))
    )
    (net (code "69") (name "unconnected-(U3-CTS-Pad23)") (class "Default")
      (node (ref "U3") (pin "23") (pinfunction "CTS_23") (pintype "passive"))
    )
    (net (code "70") (name "unconnected-(U3-DCD-Pad1)") (class "Default")
      (node (ref "U3") (pin "1") (pinfunction "DCD_1") (pintype "passive"))
    )
    (net (code "71") (name "unconnected-(U3-DSR-Pad27)") (class "Default")
      (node (ref "U3") (pin "27") (pinfunction "DSR_27") (pintype "passive"))
    )
    (net (code "72") (name "unconnected-(U3-DTR-Pad28)") (class "Default")
      (node (ref "U3") (pin "28") (pinfunction "DTR_28") (pintype "passive"))
    )
    (net (code "73") (name "unconnected-(U3-R1-Pad2)") (class "Default")
      (node (ref "U3") (pin "2") (pinfunction "R1_2") (pintype "passive"))
    )
    (net (code "74") (name "unconnected-(U3-RTS-Pad24)") (class "Default")
      (node (ref "U3") (pin "24") (pinfunction "RTS_24") (pintype "passive"))
    )
    (net (code "75") (name "unconnected-(U3-SUSPEND-Pad11)") (class "Default")
      (node (ref "U3") (pin "11") (pinfunction "SUSPEND_11") (pintype "passive"))
    )
    (net (code "76") (name "unconnected-(U3-~{SUSPEND}-Pad12)") (class "Default")
      (node (ref "U3") (pin "12") (pinfunction "~{SUSPEND}_12") (pintype "passive"))
    )
    (net (code "77") (name "unconnected-(USB_C1-SBU1-Pad9)") (class "Default")
      (node (ref "USB_C1") (pin "9") (pinfunction "SBU1_9") (pintype "passive"))
    )
    (net (code "78") (name "unconnected-(USB_C1-SBU2-Pad3)") (class "Default")
      (node (ref "USB_C1") (pin "3") (pinfunction "SBU2_3") (pintype "passive"))
    )
    (net (code "79") (name "unconnected-(USB_C2-CC1-Pad4)") (class "Default")
      (node (ref "USB_C2") (pin "4") (pinfunction "CC1_4") (pintype "passive"))
    )
    (net (code "80") (name "unconnected-(USB_C2-CC2-Pad10)") (class "Default")
      (node (ref "USB_C2") (pin "10") (pinfunction "CC2_10") (pintype "passive"))
    )
    (net (code "81") (name "unconnected-(USB_C2-SBU1-Pad9)") (class "Default")
      (node (ref "USB_C2") (pin "9") (pinfunction "SBU1_9") (pintype "passive"))
    )
    (net (code "82") (name "unconnected-(USB_C2-SBU2-Pad3)") (class "Default")
      (node (ref "USB_C2") (pin "3") (pinfunction "SBU2_3") (pintype "passive"))
    )
  )
)
